# Signal_Conditioner.net
KiCad netlist of a schematic drawn in Altium Designer
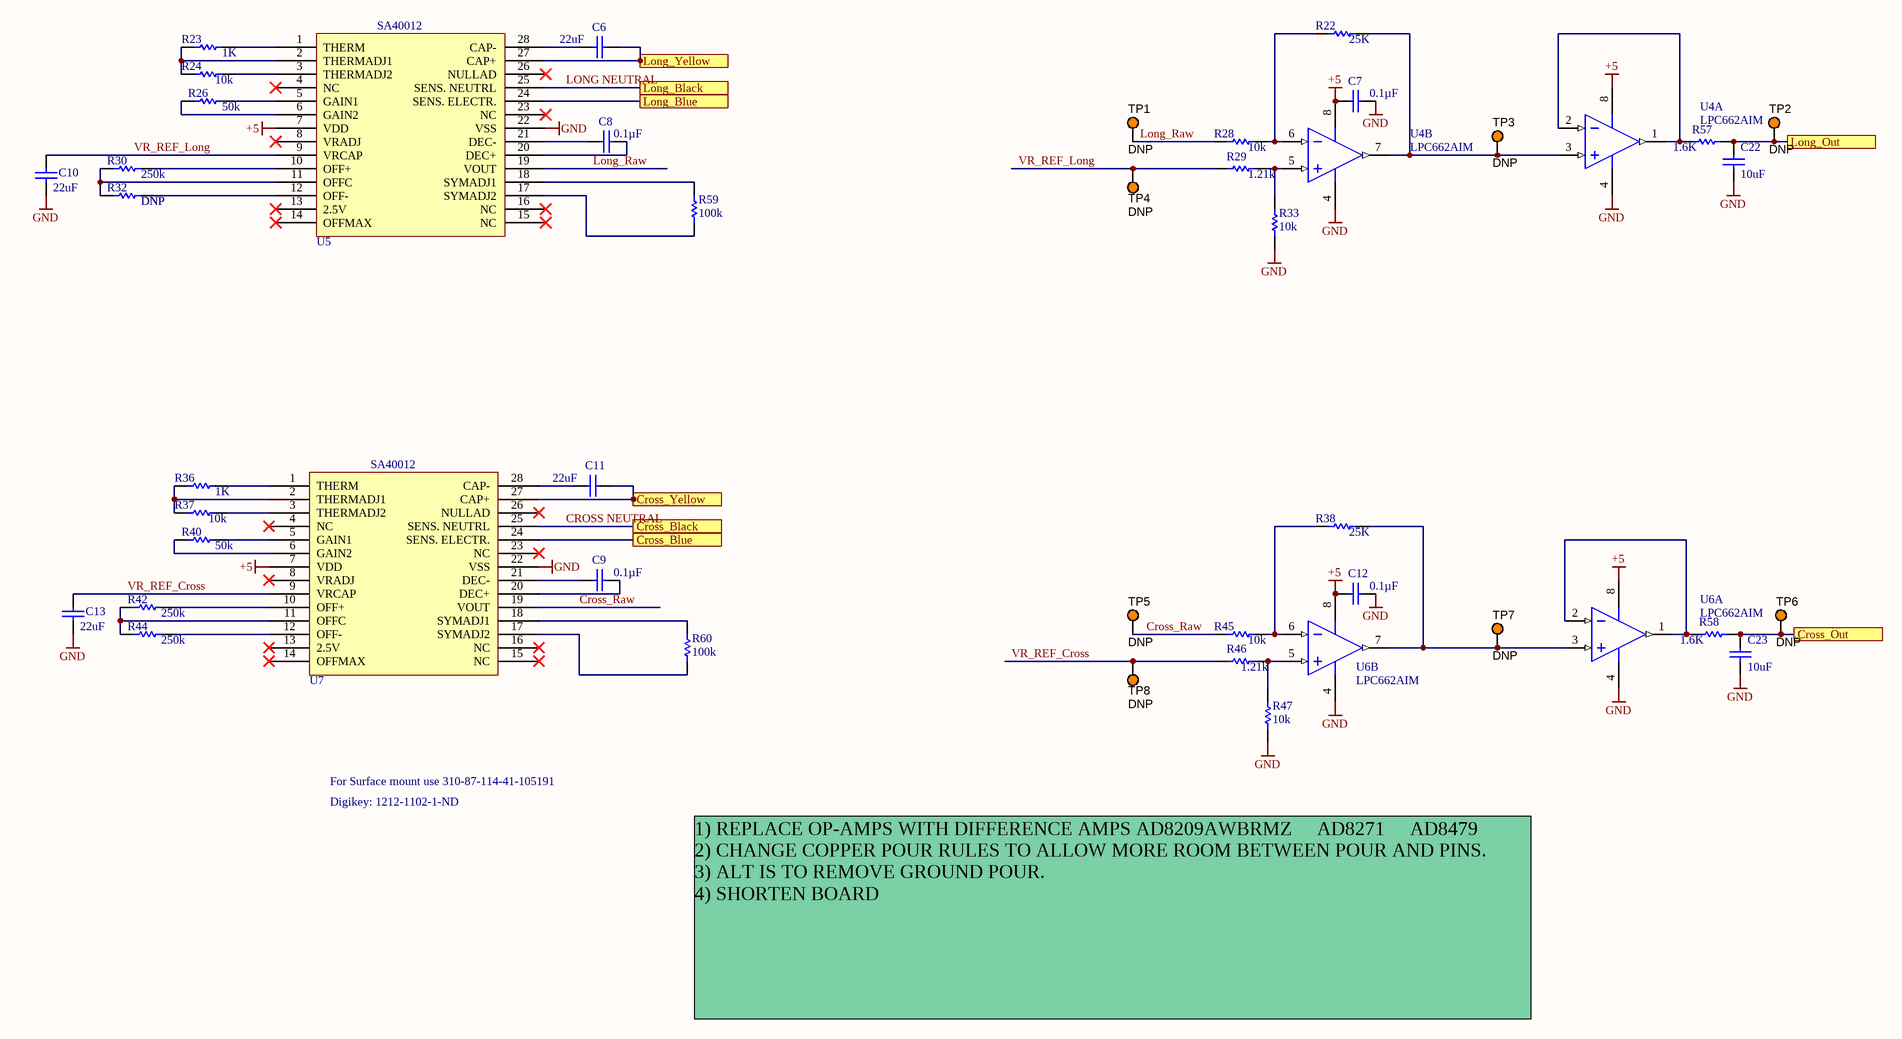
[diagram p0: Signal_Conditioner.SchDoc]

(export (version "E")
  (design (tool "Eeschema 10.0.6"))
  (components
    (comp (ref "C6")
      (value "22uF")
      (footprint "CAPC0805(2012)145_N")
      (description "CAP CER 22UF 16V X5R 0805")
      (fields
        (field (name "MANUFACTURER") "Murata Electronics North America")
        (field (name "MANUFACTURER PART NUMBER") "GRM219R61C226ME15L")
      )
      (libsource (lib "Altium Content Vault") (part "CMP-1036-04795-1"))
    )
    (comp (ref "C7")
      (value "CAP CER 0.1UF 25V X7R 0805")
      (footprint "CAPC0805(2012)145_N")
      (fields
        (field (name "MANUFACTURER") "Murata Electronics North America")
        (field (name "MANUFACTURER PART NUMBER") "GRM21BR71E104KA01L")
        (field (name "CAPACITANCE") "0.1µF")
        (field (name "TOLERANCE") "±10%")
      )
      (libsource (lib "Altium Content Vault") (part "CMP-1036-04795-1"))
    )
    (comp (ref "C8")
      (value "CAP CER 0.1UF 25V X7R 0805")
      (footprint "CAPC0805(2012)145_N")
      (fields
        (field (name "MANUFACTURER") "Murata Electronics North America")
        (field (name "MANUFACTURER PART NUMBER") "GRM21BR71E104KA01L")
        (field (name "CAPACITANCE") "0.1µF")
        (field (name "TOLERANCE") "±10%")
      )
      (libsource (lib "Altium Content Vault") (part "CMP-1036-04795-1"))
    )
    (comp (ref "C9")
      (value "CAP CER 0.1UF 25V X7R 0805")
      (footprint "CAPC0805(2012)145_N")
      (fields
        (field (name "MANUFACTURER") "Murata Electronics North America")
        (field (name "MANUFACTURER PART NUMBER") "GRM21BR71E104KA01L")
        (field (name "CAPACITANCE") "0.1µF")
        (field (name "TOLERANCE") "±10%")
      )
      (libsource (lib "Altium Content Vault") (part "CMP-1036-04795-1"))
    )
    (comp (ref "C10")
      (value "22uF")
      (footprint "CAPC0805(2012)145_N")
      (description "CAP CER 22UF 16V X5R 0805")
      (fields
        (field (name "MANUFACTURER") "Murata Electronics North America")
        (field (name "MANUFACTURER PART NUMBER") "GRM219R61C226ME15L")
      )
      (libsource (lib "Altium Content Vault") (part "CMP-1036-04795-1"))
    )
    (comp (ref "C11")
      (value "22uF")
      (footprint "CAPC0805(2012)145_N")
      (description "CAP CER 22UF 16V X5R 0805")
      (fields
        (field (name "MANUFACTURER") "Murata Electronics North America")
        (field (name "MANUFACTURER PART NUMBER") "GRM219R61C226ME15L")
      )
      (libsource (lib "Altium Content Vault") (part "CMP-1036-04795-1"))
    )
    (comp (ref "C12")
      (value "CAP CER 0.1UF 25V X7R 0805")
      (footprint "CAPC0805(2012)145_N")
      (fields
        (field (name "MANUFACTURER") "Murata Electronics North America")
        (field (name "MANUFACTURER PART NUMBER") "GRM21BR71E104KA01L")
        (field (name "CAPACITANCE") "0.1µF")
        (field (name "TOLERANCE") "±10%")
      )
      (libsource (lib "Altium Content Vault") (part "CMP-1036-04795-1"))
    )
    (comp (ref "C13")
      (value "22uF")
      (footprint "CAPC0805(2012)145_N")
      (description "CAP CER 22UF 16V X5R 0805")
      (fields
        (field (name "MANUFACTURER") "Murata Electronics North America")
        (field (name "MANUFACTURER PART NUMBER") "GRM219R61C226ME15L")
      )
      (libsource (lib "Altium Content Vault") (part "CMP-1036-04795-1"))
    )
    (comp (ref "C22")
      (value "10uF")
      (footprint "CAPC0805(2012)145_N")
      (description "CAP CER 10UF 16V X6S 0805")
      (fields
        (field (name "MANUFACTURER") "TDK Corporation")
        (field (name "MANUFACTURER PART NUMBER") "C2012X6S1C106K085AC")
      )
      (libsource (lib "Altium Content Vault") (part "CMP-1036-04795-1"))
    )
    (comp (ref "C23")
      (value "10uF")
      (footprint "CAPC0805(2012)145_N")
      (description "CAP CER 10UF 16V X6S 0805")
      (fields
        (field (name "MANUFACTURER") "TDK Corporation")
        (field (name "MANUFACTURER PART NUMBER") "C2012X6S1C106K085AC")
      )
      (libsource (lib "Altium Content Vault") (part "CMP-1036-04795-1"))
    )
    (comp (ref "R22")
      (value "25K")
      (footprint "RESC0805(2012)_L")
      (description "CRCW080510K0FKEA")
      (libsource (lib "Altium Content Vault") (part "CMP-1013-00393-1"))
    )
    (comp (ref "R23")
      (value "1K")
      (footprint "RESC0805(2012)_L")
      (description "RES SMD 1K OHM 1% 1/8W 0805")
      (fields
        (field (name "MANUFACTURER") "Vishay Dale")
        (field (name "MANUFACTURER PART NUMBER") "CRCW08051K00FKEA")
      )
      (libsource (lib "Altium Content Vault") (part "CMP-1013-00393-1"))
    )
    (comp (ref "R24")
      (value "10k")
      (footprint "RESC0805(2012)_L")
      (description "RES SMD 10K OHM 1% 1/8W 0805")
      (fields
        (field (name "MANUFACTURER") "Vishay Dale")
        (field (name "MANUFACTURER PART NUMBER") "CRCW080510K0FKEA")
      )
      (libsource (lib "Altium Content Vault") (part "CMP-1013-00393-1"))
    )
    (comp (ref "R26")
      (value "50k")
      (footprint "RESC0805(2012)_L")
      (description "RES SMD 24.3K OHM 1% 1/8W 0805")
      (fields
        (field (name "MANUFACTURER") "Vishay Dale")
        (field (name "MANUFACTURER PART NUMBER") "CRCW080524K3FKEA")
      )
      (libsource (lib "Altium Content Vault") (part "CMP-1013-00393-1"))
    )
    (comp (ref "R28")
      (value "10k")
      (footprint "RESC0805(2012)_L")
      (description "RES SMD 10K OHM 1% 1/8W 0805")
      (fields
        (field (name "MANUFACTURER") "Vishay Dale")
        (field (name "MANUFACTURER PART NUMBER") "CRCW080510K0FKEA")
      )
      (libsource (lib "Altium Content Vault") (part "CMP-1013-00393-1"))
    )
    (comp (ref "R29")
      (value "1.21k")
      (footprint "RESC0805(2012)_L")
      (description "RES SMD 1.21K OHM 1% 1/8W 0805")
      (fields
        (field (name "MANUFACTURER") "Vishay Dale")
        (field (name "MANUFACTURER PART NUMBER") "CRCW08051K21FKEA")
      )
      (libsource (lib "Altium Content Vault") (part "CMP-1013-00393-1"))
    )
    (comp (ref "R30")
      (value "250k")
      (footprint "RESC0805(2012)_L")
      (description "RES SMD 249K OHM 1% 1/8W 0805")
      (fields
        (field (name "MANUFACTURER") "Vishay Dale")
        (field (name "MANUFACTURER PART NUMBER") "CRCW0805249KFKECC")
      )
      (libsource (lib "Altium Content Vault") (part "CMP-1013-00393-1"))
    )
    (comp (ref "R32")
      (value "DNP")
      (footprint "RESC0805(2012)_L")
      (description "RES SMD 249K OHM 1% 1/8W 0805")
      (fields
        (field (name "MANUFACTURER") "Vishay Dale")
        (field (name "MANUFACTURER PART NUMBER") "CRCW0805249KFKECC")
      )
      (libsource (lib "Altium Content Vault") (part "CMP-1013-00393-1"))
    )
    (comp (ref "R33")
      (value "10k")
      (footprint "RESC0805(2012)_L")
      (description "RES SMD 10K OHM 1% 1/8W 0805")
      (fields
        (field (name "MANUFACTURER") "Vishay Dale")
        (field (name "MANUFACTURER PART NUMBER") "CRCW080510K0FKEA")
      )
      (libsource (lib "Altium Content Vault") (part "CMP-1013-00393-1"))
    )
    (comp (ref "R36")
      (value "1K")
      (footprint "RESC0805(2012)_L")
      (description "RES SMD 1K OHM 1% 1/8W 0805")
      (fields
        (field (name "MANUFACTURER") "Vishay Dale")
        (field (name "MANUFACTURER PART NUMBER") "CRCW08051K00FKEA")
      )
      (libsource (lib "Altium Content Vault") (part "CMP-1013-00393-1"))
    )
    (comp (ref "R37")
      (value "10k")
      (footprint "RESC0805(2012)_L")
      (description "RES SMD 10K OHM 1% 1/8W 0805")
      (fields
        (field (name "MANUFACTURER") "Vishay Dale")
        (field (name "MANUFACTURER PART NUMBER") "CRCW080510K0FKEA")
      )
      (libsource (lib "Altium Content Vault") (part "CMP-1013-00393-1"))
    )
    (comp (ref "R38")
      (value "25K")
      (footprint "RESC0805(2012)_L")
      (description "CRCW080510K0FKEA")
      (libsource (lib "Altium Content Vault") (part "CMP-1013-00393-1"))
    )
    (comp (ref "R40")
      (value "50k")
      (footprint "RESC0805(2012)_L")
      (description "RES SMD 24.3K OHM 1% 1/8W 0805")
      (fields
        (field (name "MANUFACTURER") "Vishay Dale")
        (field (name "MANUFACTURER PART NUMBER") "CRCW080524K3FKEA")
      )
      (libsource (lib "Altium Content Vault") (part "CMP-1013-00393-1"))
    )
    (comp (ref "R42")
      (value "250k")
      (footprint "RESC0805(2012)_L")
      (description "RES SMD 249K OHM 1% 1/8W 0805")
      (fields
        (field (name "MANUFACTURER") "Vishay Dale")
        (field (name "MANUFACTURER PART NUMBER") "CRCW0805249KFKECC")
      )
      (libsource (lib "Altium Content Vault") (part "CMP-1013-00393-1"))
    )
    (comp (ref "R44")
      (value "250k")
      (footprint "RESC0805(2012)_L")
      (description "RES SMD 249K OHM 1% 1/8W 0805")
      (fields
        (field (name "MANUFACTURER") "Vishay Dale")
        (field (name "MANUFACTURER PART NUMBER") "CRCW0805249KFKECC")
      )
      (libsource (lib "Altium Content Vault") (part "CMP-1013-00393-1"))
    )
    (comp (ref "R45")
      (value "10k")
      (footprint "RESC0805(2012)_L")
      (description "RES SMD 10K OHM 1% 1/8W 0805")
      (fields
        (field (name "MANUFACTURER") "Vishay Dale")
        (field (name "MANUFACTURER PART NUMBER") "CRCW080510K0FKEA")
      )
      (libsource (lib "Altium Content Vault") (part "CMP-1013-00393-1"))
    )
    (comp (ref "R46")
      (value "1.21k")
      (footprint "RESC0805(2012)_L")
      (description "RES SMD 1.21K OHM 1% 1/8W 0805")
      (fields
        (field (name "MANUFACTURER") "Vishay Dale")
        (field (name "MANUFACTURER PART NUMBER") "CRCW08051K21FKEA")
      )
      (libsource (lib "Altium Content Vault") (part "CMP-1013-00393-1"))
    )
    (comp (ref "R47")
      (value "10k")
      (footprint "RESC0805(2012)_L")
      (description "RES SMD 10K OHM 1% 1/8W 0805")
      (fields
        (field (name "MANUFACTURER") "Vishay Dale")
        (field (name "MANUFACTURER PART NUMBER") "CRCW080510K0FKEA")
      )
      (libsource (lib "Altium Content Vault") (part "CMP-1013-00393-1"))
    )
    (comp (ref "R57")
      (value "1.6K")
      (footprint "RESC0805(2012)_N")
      (description "RES SMD 1.6K OHM 1% 1/8W 0805")
      (libsource (lib "Altium Content Vault") (part "CMP-1013-00606-1"))
    )
    (comp (ref "R58")
      (value "1.6K")
      (footprint "RESC0805(2012)_N")
      (description "RES SMD 1.6K OHM 1% 1/8W 0805")
      (libsource (lib "Altium Content Vault") (part "CMP-1013-00606-1"))
    )
    (comp (ref "R59")
      (value "100k")
      (footprint "RESC0805(2012)_L")
      (description "RES SMD 50K OHM 1% 1/8W 0805")
      (fields (field (name "TOLERANCE") "±1%"))
      (libsource (lib "Altium Content Vault") (part "CMP-1013-00393-1"))
    )
    (comp (ref "R60")
      (value "100k")
      (footprint "RESC0805(2012)_L")
      (description "RES SMD 50K OHM 1% 1/8W 0805")
      (fields (field (name "TOLERANCE") "±1%"))
      (libsource (lib "Altium Content Vault") (part "CMP-1013-00393-1"))
    )
    (comp (ref "TP1")
      (value "DNP")
      (footprint "KSTN-5003")
      (description "Test Point, Orange, 1-Pin THD, RoHS")
      (fields
        (field (name "MANUFACTURER") "Keystone Electronics")
        (field (name "MANUFACTURER PART NUMBER") "5003")
      )
      (libsource (lib "Altium Content Vault") (part "CMP-1672-00009-1"))
    )
    (comp (ref "TP2")
      (value "DNP")
      (footprint "KSTN-5003")
      (description "Test Point, Orange, 1-Pin THD, RoHS")
      (fields
        (field (name "MANUFACTURER") "Keystone Electronics")
        (field (name "MANUFACTURER PART NUMBER") "5003")
      )
      (libsource (lib "Altium Content Vault") (part "CMP-1672-00009-1"))
    )
    (comp (ref "TP3")
      (value "DNP")
      (footprint "KSTN-5003")
      (description "Test Point, Orange, 1-Pin THD, RoHS")
      (fields
        (field (name "MANUFACTURER") "Keystone Electronics")
        (field (name "MANUFACTURER PART NUMBER") "5003")
      )
      (libsource (lib "Altium Content Vault") (part "CMP-1672-00009-1"))
    )
    (comp (ref "TP4")
      (value "DNP")
      (footprint "KSTN-5003")
      (description "Test Point, Orange, 1-Pin THD, RoHS")
      (fields
        (field (name "MANUFACTURER") "Keystone Electronics")
        (field (name "MANUFACTURER PART NUMBER") "5003")
      )
      (libsource (lib "Altium Content Vault") (part "CMP-1672-00009-1"))
    )
    (comp (ref "TP5")
      (value "DNP")
      (footprint "KSTN-5003")
      (description "Test Point, Orange, 1-Pin THD, RoHS")
      (fields
        (field (name "MANUFACTURER") "Keystone Electronics")
        (field (name "MANUFACTURER PART NUMBER") "5003")
      )
      (libsource (lib "Altium Content Vault") (part "CMP-1672-00009-1"))
    )
    (comp (ref "TP6")
      (value "DNP")
      (footprint "KSTN-5003")
      (description "Test Point, Orange, 1-Pin THD, RoHS")
      (fields
        (field (name "MANUFACTURER") "Keystone Electronics")
        (field (name "MANUFACTURER PART NUMBER") "5003")
      )
      (libsource (lib "Altium Content Vault") (part "CMP-1672-00009-1"))
    )
    (comp (ref "TP7")
      (value "DNP")
      (footprint "KSTN-5003")
      (description "Test Point, Orange, 1-Pin THD, RoHS")
      (fields
        (field (name "MANUFACTURER") "Keystone Electronics")
        (field (name "MANUFACTURER PART NUMBER") "5003")
      )
      (libsource (lib "Altium Content Vault") (part "CMP-1672-00009-1"))
    )
    (comp (ref "TP8")
      (value "DNP")
      (footprint "KSTN-5003")
      (description "Test Point, Orange, 1-Pin THD, RoHS")
      (fields
        (field (name "MANUFACTURER") "Keystone Electronics")
        (field (name "MANUFACTURER PART NUMBER") "5003")
      )
      (libsource (lib "Altium Content Vault") (part "CMP-1672-00009-1"))
    )
    (comp (ref "U4")
      (value "LPC662AIM")
      (footprint "D0008A_M")
      (description "Low Power CMOS Dual Operational Amplifier, 8-pin Narrow SOIC")
      (fields (field (name "MANUFACTURER") "Texas Instruments"))
      (libsource (lib "Altium Content Vault") (part "AMP-OPA-LM6132-8"))
    )
    (comp (ref "U5")
      (value "SA40012")
      (footprint "SA40012")
      (description "Single Axix CMOS Signal Conditioning Module")
      (fields (field (name "MANUFACTURER") "Spectron") (field (name "MANUFACTURER PART NUMBER") "A40012"))
      (libsource (lib "ZLS_Schematic_lib") (part "SA40012"))
    )
    (comp (ref "U6")
      (value "LPC662AIM")
      (footprint "D0008A_M")
      (description "Low Power CMOS Dual Operational Amplifier, 8-pin Narrow SOIC")
      (fields
        (field (name "MANUFACTURER") "Texas Instruments")
        (field (name "MANUFACTURER PART NUMBER") "LPC662AIMX/NOPB")
      )
      (libsource (lib "Altium Content Vault") (part "CMP-0055-00867-3"))
    )
    (comp (ref "U7")
      (value "SA40012")
      (footprint "SA40012")
      (description "Single Axix CMOS Signal Conditioning Module")
      (fields (field (name "MANUFACTURER") "Spectron") (field (name "MANUFACTURER PART NUMBER") "A40012"))
      (libsource (lib "ZLS_Schematic_lib") (part "SA40012"))
    )
  )
  (nets
    (net (code "1") (name "+5") (class "Default")
      (node (ref "C12") (pin "1") (pinfunction "1_1") (pintype "passive"))
      (node (ref "C7") (pin "1") (pinfunction "1_1") (pintype "passive"))
      (node (ref "U4") (pin "8") (pinfunction "V+_8") (pintype "power_in"))
      (node (ref "U5") (pin "7") (pinfunction "VDD_7") (pintype "passive"))
      (node (ref "U6") (pin "8") (pinfunction "V+_8") (pintype "power_in"))
      (node (ref "U7") (pin "7") (pinfunction "VDD_7") (pintype "passive"))
    )
    (net (code "2") (name "/CROSS NEUTRAL") (class "Default")
      (node (ref "U7") (pin "25") (pinfunction "SENS._NEUTRL_25") (pintype "passive"))
    )
    (net (code "3") (name "/Cross_Blue") (class "Default")
      (node (ref "U7") (pin "24") (pinfunction "SENS._ELECTR._24") (pintype "passive"))
    )
    (net (code "4") (name "/Cross_Out") (class "Default")
      (node (ref "C23") (pin "1") (pinfunction "1_1") (pintype "passive"))
      (node (ref "R58") (pin "1") (pinfunction "1_1") (pintype "passive"))
      (node (ref "TP6") (pin "1") (pinfunction "1_1") (pintype "passive"))
    )
    (net (code "5") (name "/Cross_Raw") (class "Default")
      (node (ref "R45") (pin "1") (pinfunction "1_1") (pintype "passive"))
      (node (ref "TP5") (pin "1") (pinfunction "1_1") (pintype "passive"))
      (node (ref "U7") (pin "19") (pinfunction "VOUT_19") (pintype "passive"))
    )
    (net (code "6") (name "/Cross_Yellow") (class "Default")
      (node (ref "C11") (pin "2") (pinfunction "2_2") (pintype "passive"))
      (node (ref "U7") (pin "27") (pinfunction "CAP+_27") (pintype "passive"))
    )
    (net (code "7") (name "/LONG NEUTRAL") (class "Default")
      (node (ref "U5") (pin "25") (pinfunction "SENS._NEUTRL_25") (pintype "passive"))
    )
    (net (code "8") (name "/Long_Blue") (class "Default")
      (node (ref "U5") (pin "24") (pinfunction "SENS._ELECTR._24") (pintype "passive"))
    )
    (net (code "9") (name "/Long_Out") (class "Default")
      (node (ref "C22") (pin "1") (pinfunction "1_1") (pintype "passive"))
      (node (ref "R57") (pin "1") (pinfunction "1_1") (pintype "passive"))
      (node (ref "TP2") (pin "1") (pinfunction "1_1") (pintype "passive"))
    )
    (net (code "10") (name "/Long_Raw") (class "Default")
      (node (ref "R28") (pin "1") (pinfunction "1_1") (pintype "passive"))
      (node (ref "TP1") (pin "1") (pinfunction "1_1") (pintype "passive"))
      (node (ref "U5") (pin "19") (pinfunction "VOUT_19") (pintype "passive"))
    )
    (net (code "11") (name "/Long_Yellow") (class "Default")
      (node (ref "C6") (pin "2") (pinfunction "2_2") (pintype "passive"))
      (node (ref "U5") (pin "27") (pinfunction "CAP+_27") (pintype "passive"))
    )
    (net (code "12") (name "/VR_REF_Cross") (class "Default")
      (node (ref "C13") (pin "1") (pinfunction "1_1") (pintype "passive"))
      (node (ref "R46") (pin "2") (pinfunction "2_2") (pintype "passive"))
      (node (ref "TP8") (pin "1") (pinfunction "1_1") (pintype "passive"))
      (node (ref "U7") (pin "9") (pinfunction "VRCAP_9") (pintype "passive"))
    )
    (net (code "13") (name "/VR_REF_Long") (class "Default")
      (node (ref "C10") (pin "1") (pinfunction "1_1") (pintype "passive"))
      (node (ref "R29") (pin "2") (pinfunction "2_2") (pintype "passive"))
      (node (ref "TP4") (pin "1") (pinfunction "1_1") (pintype "passive"))
      (node (ref "U5") (pin "9") (pinfunction "VRCAP_9") (pintype "passive"))
    )
    (net (code "14") (name "GND") (class "Default")
      (node (ref "C10") (pin "2") (pinfunction "2_2") (pintype "passive"))
      (node (ref "C12") (pin "2") (pinfunction "2_2") (pintype "passive"))
      (node (ref "C13") (pin "2") (pinfunction "2_2") (pintype "passive"))
      (node (ref "C22") (pin "2") (pinfunction "2_2") (pintype "passive"))
      (node (ref "C23") (pin "2") (pinfunction "2_2") (pintype "passive"))
      (node (ref "C7") (pin "2") (pinfunction "2_2") (pintype "passive"))
      (node (ref "R33") (pin "1") (pinfunction "1_1") (pintype "passive"))
      (node (ref "R47") (pin "1") (pinfunction "1_1") (pintype "passive"))
      (node (ref "U4") (pin "4") (pinfunction "V-_4") (pintype "power_in"))
      (node (ref "U5") (pin "22") (pinfunction "VSS_22") (pintype "passive"))
      (node (ref "U6") (pin "4") (pinfunction "V-_4") (pintype "power_in"))
      (node (ref "U7") (pin "22") (pinfunction "VSS_22") (pintype "passive"))
    )
    (net (code "15") (name "Net-(U4A-INA+)") (class "Default")
      (node (ref "R22") (pin "2") (pinfunction "2_2") (pintype "passive"))
      (node (ref "TP3") (pin "1") (pinfunction "1_1") (pintype "passive"))
      (node (ref "U4") (pin "3") (pinfunction "INA+_3") (pintype "input"))
      (node (ref "U4") (pin "7") (pinfunction "OUTB_7") (pintype "output"))
    )
    (net (code "16") (name "Net-(U4A-INA-)") (class "Default")
      (node (ref "R57") (pin "2") (pinfunction "2_2") (pintype "passive"))
      (node (ref "U4") (pin "1") (pinfunction "OUTA_1") (pintype "output"))
      (node (ref "U4") (pin "2") (pinfunction "INA-_2") (pintype "input"))
    )
    (net (code "17") (name "Net-(U4B-INB+)") (class "Default")
      (node (ref "R29") (pin "1") (pinfunction "1_1") (pintype "passive"))
      (node (ref "R33") (pin "2") (pinfunction "2_2") (pintype "passive"))
      (node (ref "U4") (pin "5") (pinfunction "INB+_5") (pintype "input"))
    )
    (net (code "18") (name "Net-(U4B-INB-)") (class "Default")
      (node (ref "R22") (pin "1") (pinfunction "1_1") (pintype "passive"))
      (node (ref "R28") (pin "2") (pinfunction "2_2") (pintype "passive"))
      (node (ref "U4") (pin "6") (pinfunction "INB-_6") (pintype "input"))
    )
    (net (code "19") (name "Net-(U5-CAP-)") (class "Default")
      (node (ref "C6") (pin "1") (pinfunction "1_1") (pintype "passive"))
      (node (ref "U5") (pin "28") (pinfunction "CAP-_28") (pintype "passive"))
    )
    (net (code "20") (name "Net-(U5-DEC+)") (class "Default")
      (node (ref "C8") (pin "2") (pinfunction "2_2") (pintype "passive"))
      (node (ref "U5") (pin "20") (pinfunction "DEC+_20") (pintype "passive"))
    )
    (net (code "21") (name "Net-(U5-DEC-)") (class "Default")
      (node (ref "C8") (pin "1") (pinfunction "1_1") (pintype "passive"))
      (node (ref "U5") (pin "21") (pinfunction "DEC-_21") (pintype "passive"))
    )
    (net (code "22") (name "Net-(U5-GAIN1)") (class "Default")
      (node (ref "R26") (pin "2") (pinfunction "2_2") (pintype "passive"))
      (node (ref "U5") (pin "5") (pinfunction "GAIN1_5") (pintype "passive"))
    )
    (net (code "23") (name "Net-(U5-GAIN2)") (class "Default")
      (node (ref "R26") (pin "1") (pinfunction "1_1") (pintype "passive"))
      (node (ref "U5") (pin "6") (pinfunction "GAIN2_6") (pintype "passive"))
    )
    (net (code "24") (name "Net-(U5-OFF+)") (class "Default")
      (node (ref "R30") (pin "2") (pinfunction "2_2") (pintype "passive"))
      (node (ref "U5") (pin "10") (pinfunction "OFF+_10") (pintype "passive"))
    )
    (net (code "25") (name "Net-(U5-OFF-)") (class "Default")
      (node (ref "R32") (pin "2") (pinfunction "2_2") (pintype "passive"))
      (node (ref "U5") (pin "12") (pinfunction "OFF-_12") (pintype "passive"))
    )
    (net (code "26") (name "Net-(U5-OFFC)") (class "Default")
      (node (ref "R30") (pin "1") (pinfunction "1_1") (pintype "passive"))
      (node (ref "R32") (pin "1") (pinfunction "1_1") (pintype "passive"))
      (node (ref "U5") (pin "11") (pinfunction "OFFC_11") (pintype "passive"))
    )
    (net (code "27") (name "Net-(U5-SYMADJ1)") (class "Default")
      (node (ref "R59") (pin "2") (pinfunction "2_2") (pintype "passive"))
      (node (ref "U5") (pin "18") (pinfunction "SYMADJ1_18") (pintype "passive"))
    )
    (net (code "28") (name "Net-(U5-SYMADJ2)") (class "Default")
      (node (ref "R59") (pin "1") (pinfunction "1_1") (pintype "passive"))
      (node (ref "U5") (pin "17") (pinfunction "SYMADJ2_17") (pintype "passive"))
    )
    (net (code "29") (name "Net-(U5-THERM)") (class "Default")
      (node (ref "R23") (pin "2") (pinfunction "2_2") (pintype "passive"))
      (node (ref "U5") (pin "1") (pinfunction "THERM_1") (pintype "passive"))
    )
    (net (code "30") (name "Net-(U5-THERMADJ1)") (class "Default")
      (node (ref "R23") (pin "1") (pinfunction "1_1") (pintype "passive"))
      (node (ref "R24") (pin "1") (pinfunction "1_1") (pintype "passive"))
      (node (ref "U5") (pin "2") (pinfunction "THERMADJ1_2") (pintype "passive"))
    )
    (net (code "31") (name "Net-(U5-THERMADJ2)") (class "Default")
      (node (ref "R24") (pin "2") (pinfunction "2_2") (pintype "passive"))
      (node (ref "U5") (pin "3") (pinfunction "THERMADJ2_3") (pintype "passive"))
    )
    (net (code "32") (name "Net-(U6A-INA+)") (class "Default")
      (node (ref "R38") (pin "2") (pinfunction "2_2") (pintype "passive"))
      (node (ref "TP7") (pin "1") (pinfunction "1_1") (pintype "passive"))
      (node (ref "U6") (pin "3") (pinfunction "INA+_3") (pintype "input"))
      (node (ref "U6") (pin "7") (pinfunction "OUTB_7") (pintype "output"))
    )
    (net (code "33") (name "Net-(U6A-INA-)") (class "Default")
      (node (ref "R58") (pin "2") (pinfunction "2_2") (pintype "passive"))
      (node (ref "U6") (pin "1") (pinfunction "OUTA_1") (pintype "output"))
      (node (ref "U6") (pin "2") (pinfunction "INA-_2") (pintype "input"))
    )
    (net (code "34") (name "Net-(U6B-INB+)") (class "Default")
      (node (ref "R46") (pin "1") (pinfunction "1_1") (pintype "passive"))
      (node (ref "R47") (pin "2") (pinfunction "2_2") (pintype "passive"))
      (node (ref "U6") (pin "5") (pinfunction "INB+_5") (pintype "input"))
    )
    (net (code "35") (name "Net-(U6B-INB-)") (class "Default")
      (node (ref "R38") (pin "1") (pinfunction "1_1") (pintype "passive"))
      (node (ref "R45") (pin "2") (pinfunction "2_2") (pintype "passive"))
      (node (ref "U6") (pin "6") (pinfunction "INB-_6") (pintype "input"))
    )
    (net (code "36") (name "Net-(U7-CAP-)") (class "Default")
      (node (ref "C11") (pin "1") (pinfunction "1_1") (pintype "passive"))
      (node (ref "U7") (pin "28") (pinfunction "CAP-_28") (pintype "passive"))
    )
    (net (code "37") (name "Net-(U7-DEC+)") (class "Default")
      (node (ref "C9") (pin "2") (pinfunction "2_2") (pintype "passive"))
      (node (ref "U7") (pin "20") (pinfunction "DEC+_20") (pintype "passive"))
    )
    (net (code "38") (name "Net-(U7-DEC-)") (class "Default")
      (node (ref "C9") (pin "1") (pinfunction "1_1") (pintype "passive"))
      (node (ref "U7") (pin "21") (pinfunction "DEC-_21") (pintype "passive"))
    )
    (net (code "39") (name "Net-(U7-GAIN1)") (class "Default")
      (node (ref "R40") (pin "2") (pinfunction "2_2") (pintype "passive"))
      (node (ref "U7") (pin "5") (pinfunction "GAIN1_5") (pintype "passive"))
    )
    (net (code "40") (name "Net-(U7-GAIN2)") (class "Default")
      (node (ref "R40") (pin "1") (pinfunction "1_1") (pintype "passive"))
      (node (ref "U7") (pin "6") (pinfunction "GAIN2_6") (pintype "passive"))
    )
    (net (code "41") (name "Net-(U7-OFF+)") (class "Default")
      (node (ref "R42") (pin "2") (pinfunction "2_2") (pintype "passive"))
      (node (ref "U7") (pin "10") (pinfunction "OFF+_10") (pintype "passive"))
    )
    (net (code "42") (name "Net-(U7-OFF-)") (class "Default")
      (node (ref "R44") (pin "2") (pinfunction "2_2") (pintype "passive"))
      (node (ref "U7") (pin "12") (pinfunction "OFF-_12") (pintype "passive"))
    )
    (net (code "43") (name "Net-(U7-OFFC)") (class "Default")
      (node (ref "R42") (pin "1") (pinfunction "1_1") (pintype "passive"))
      (node (ref "R44") (pin "1") (pinfunction "1_1") (pintype "passive"))
      (node (ref "U7") (pin "11") (pinfunction "OFFC_11") (pintype "passive"))
    )
    (net (code "44") (name "Net-(U7-SYMADJ1)") (class "Default")
      (node (ref "R60") (pin "2") (pinfunction "2_2") (pintype "passive"))
      (node (ref "U7") (pin "18") (pinfunction "SYMADJ1_18") (pintype "passive"))
    )
    (net (code "45") (name "Net-(U7-SYMADJ2)") (class "Default")
      (node (ref "R60") (pin "1") (pinfunction "1_1") (pintype "passive"))
      (node (ref "U7") (pin "17") (pinfunction "SYMADJ2_17") (pintype "passive"))
    )
    (net (code "46") (name "Net-(U7-THERM)") (class "Default")
      (node (ref "R36") (pin "2") (pinfunction "2_2") (pintype "passive"))
      (node (ref "U7") (pin "1") (pinfunction "THERM_1") (pintype "passive"))
    )
    (net (code "47") (name "Net-(U7-THERMADJ1)") (class "Default")
      (node (ref "R36") (pin "1") (pinfunction "1_1") (pintype "passive"))
      (node (ref "R37") (pin "1") (pinfunction "1_1") (pintype "passive"))
      (node (ref "U7") (pin "2") (pinfunction "THERMADJ1_2") (pintype "passive"))
    )
    (net (code "48") (name "Net-(U7-THERMADJ2)") (class "Default")
      (node (ref "R37") (pin "2") (pinfunction "2_2") (pintype "passive"))
      (node (ref "U7") (pin "3") (pinfunction "THERMADJ2_3") (pintype "passive"))
    )
    (net (code "49") (name "unconnected-(U5-2.5V-Pad13)") (class "Default")
      (node (ref "U5") (pin "13") (pinfunction "2.5V_13") (pintype "passive+no_connect"))
    )
    (net (code "50") (name "unconnected-(U5-NC-Pad4)") (class "Default")
      (node (ref "U5") (pin "4") (pinfunction "NC_4") (pintype "passive+no_connect"))
    )
    (net (code "51") (name "unconnected-(U5-NC-Pad15)") (class "Default")
      (node (ref "U5") (pin "15") (pinfunction "NC_15") (pintype "passive+no_connect"))
    )
    (net (code "52") (name "unconnected-(U5-NC-Pad16)") (class "Default")
      (node (ref "U5") (pin "16") (pinfunction "NC_16") (pintype "passive+no_connect"))
    )
    (net (code "53") (name "unconnected-(U5-NC-Pad23)") (class "Default")
      (node (ref "U5") (pin "23") (pinfunction "NC_23") (pintype "passive+no_connect"))
    )
    (net (code "54") (name "unconnected-(U5-NULLAD-Pad26)") (class "Default")
      (node (ref "U5") (pin "26") (pinfunction "NULLAD_26") (pintype "passive+no_connect"))
    )
    (net (code "55") (name "unconnected-(U5-OFFMAX-Pad14)") (class "Default")
      (node (ref "U5") (pin "14") (pinfunction "OFFMAX_14") (pintype "passive+no_connect"))
    )
    (net (code "56") (name "unconnected-(U5-VRADJ-Pad8)") (class "Default")
      (node (ref "U5") (pin "8") (pinfunction "VRADJ_8") (pintype "passive+no_connect"))
    )
    (net (code "57") (name "unconnected-(U7-2.5V-Pad13)") (class "Default")
      (node (ref "U7") (pin "13") (pinfunction "2.5V_13") (pintype "passive+no_connect"))
    )
    (net (code "58") (name "unconnected-(U7-NC-Pad4)") (class "Default")
      (node (ref "U7") (pin "4") (pinfunction "NC_4") (pintype "passive+no_connect"))
    )
    (net (code "59") (name "unconnected-(U7-NC-Pad15)") (class "Default")
      (node (ref "U7") (pin "15") (pinfunction "NC_15") (pintype "passive+no_connect"))
    )
    (net (code "60") (name "unconnected-(U7-NC-Pad16)") (class "Default")
      (node (ref "U7") (pin "16") (pinfunction "NC_16") (pintype "passive+no_connect"))
    )
    (net (code "61") (name "unconnected-(U7-NC-Pad23)") (class "Default")
      (node (ref "U7") (pin "23") (pinfunction "NC_23") (pintype "passive+no_connect"))
    )
    (net (code "62") (name "unconnected-(U7-NULLAD-Pad26)") (class "Default")
      (node (ref "U7") (pin "26") (pinfunction "NULLAD_26") (pintype "passive+no_connect"))
    )
    (net (code "63") (name "unconnected-(U7-OFFMAX-Pad14)") (class "Default")
      (node (ref "U7") (pin "14") (pinfunction "OFFMAX_14") (pintype "passive+no_connect"))
    )
    (net (code "64") (name "unconnected-(U7-VRADJ-Pad8)") (class "Default")
      (node (ref "U7") (pin "8") (pinfunction "VRADJ_8") (pintype "passive+no_connect"))
    )
  )
)
